# MicroBlue-CPU_PSU_1_0_rdob-millable.net
KiCad netlist of a schematic drawn in EAGLE
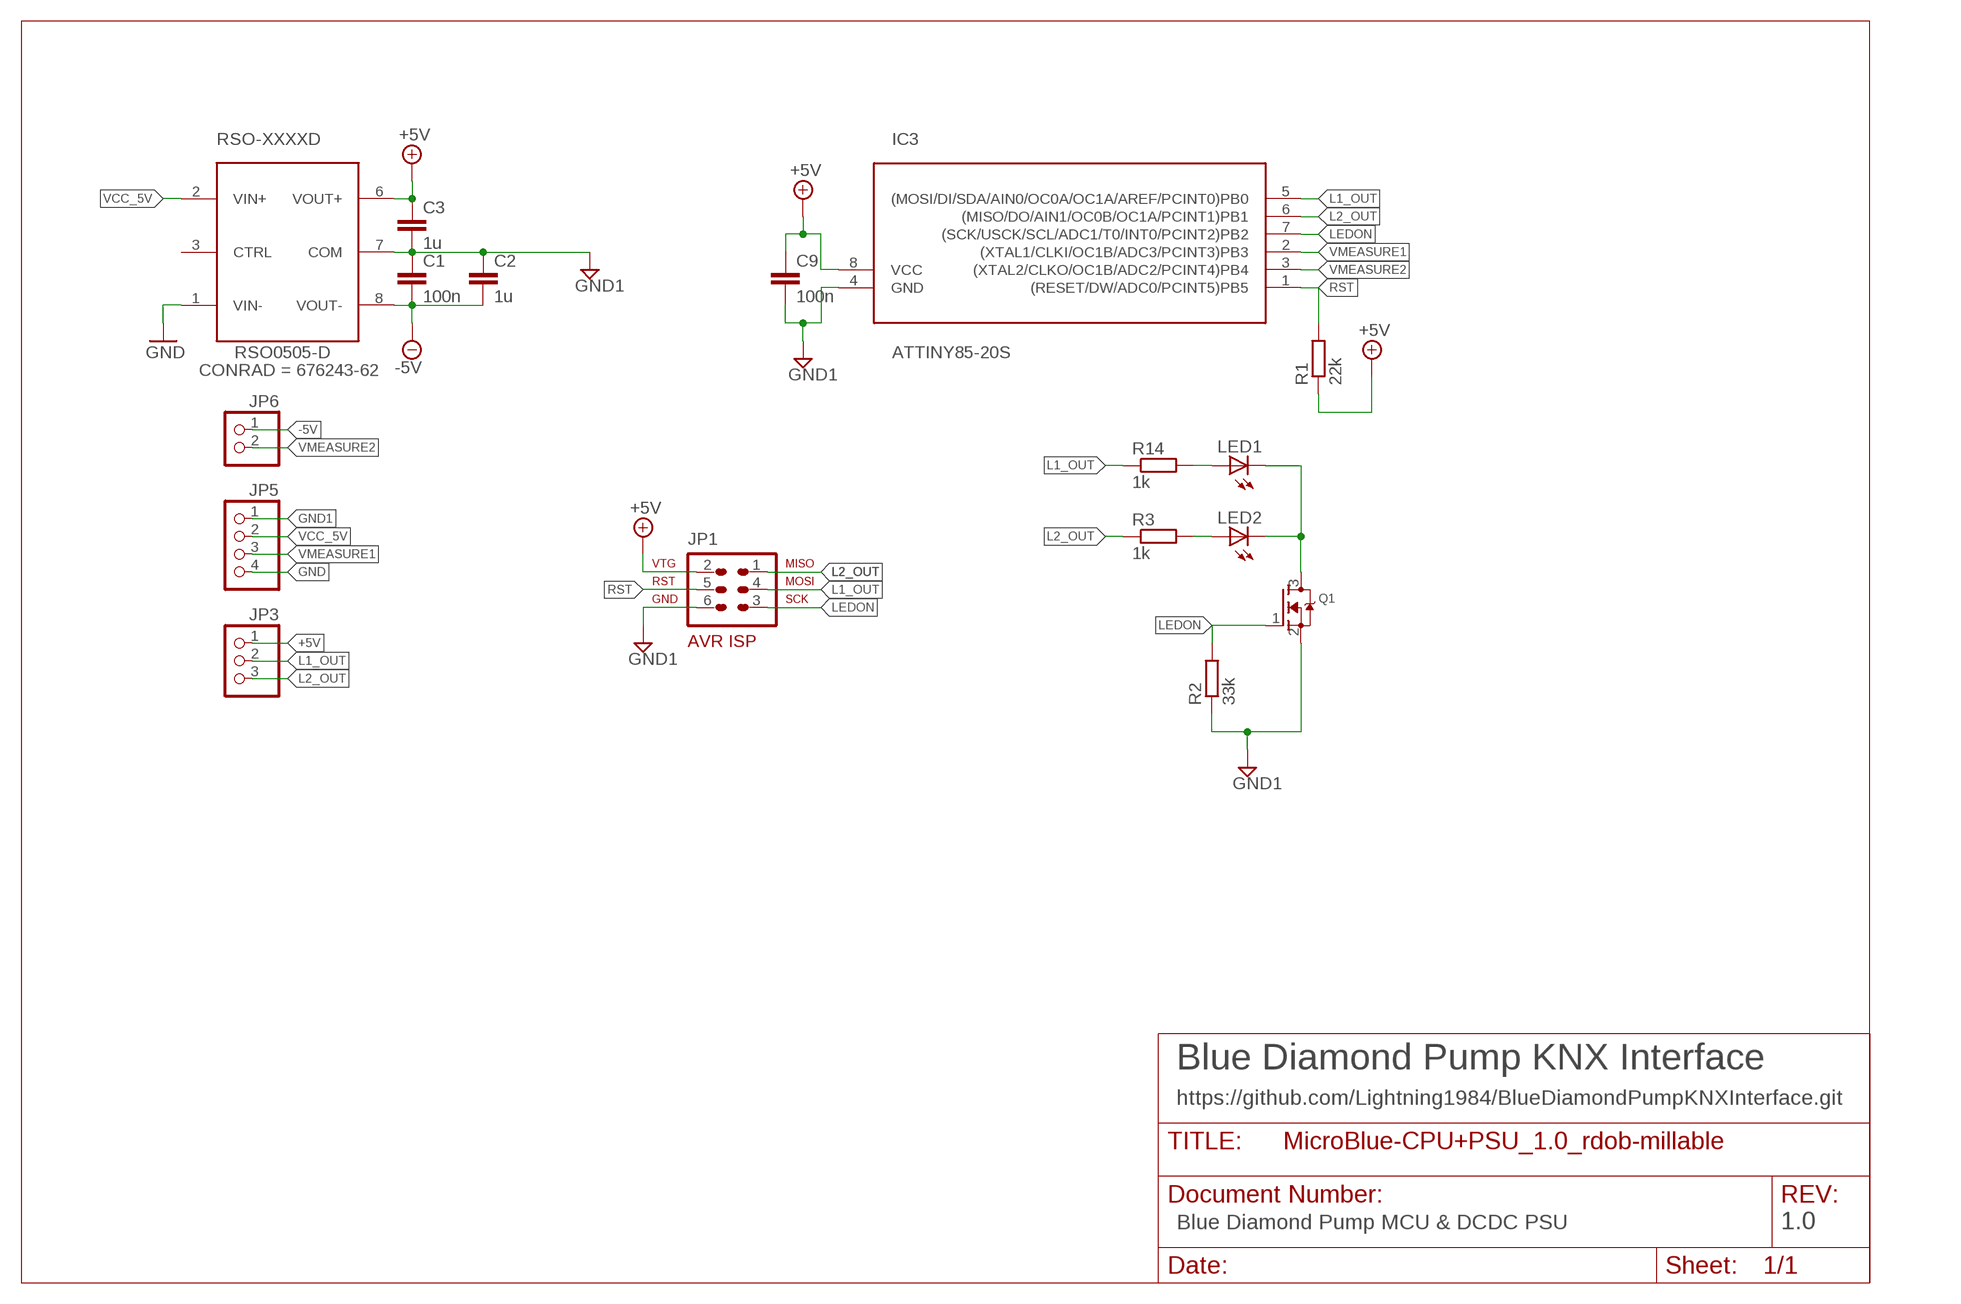
[diagram p0: schematic, sheet 1]

(export (version "E")
  (design (tool "Eeschema 10.0.6"))
  (components
    (comp (ref "C1")
      (value "100n")
      (footprint "eagle-import:C0805K")
      (libsource (lib "eagle-import") (part "C-EUC0805K"))
    )
    (comp (ref "C2")
      (value "1u")
      (footprint "eagle-import:C0805K")
      (libsource (lib "eagle-import") (part "C-EUC0805K"))
    )
    (comp (ref "C3")
      (value "1u")
      (footprint "eagle-import:C0805K")
      (libsource (lib "eagle-import") (part "C-EUC0805K"))
    )
    (comp (ref "C9")
      (value "100n")
      (footprint "eagle-import:C0805K")
      (libsource (lib "eagle-import") (part "C-EUC0805K"))
    )
    (comp (ref "IC3")
      (value "ATTINY85-20S")
      (footprint "eagle-import:SOIC8")
      (libsource (lib "eagle-import") (part "ATTINY85S-20"))
    )
    (comp (ref "JP1")
      (value "AVR-ISP-6R")
      (footprint "eagle-import:AVR-ISP-6R")
      (libsource (lib "eagle-import") (part "AVR-ISP-6R"))
    )
    (comp (ref "JP3")
      (value "PINHD-1X03_2.54-0.90MM-DRILL")
      (footprint "eagle-import:1X03-0.90DRILL")
      (libsource (lib "eagle-import") (part "PINHD-1X03_2.54-0.90MM-DRILL"))
    )
    (comp (ref "JP5")
      (value "PINHD-1X04_2.54-0.90MM-DRILL")
      (footprint "eagle-import:1X04-0.90DRILL")
      (libsource (lib "eagle-import") (part "PINHD-1X04_2.54-0.90MM-DRILL"))
    )
    (comp (ref "JP6")
      (value "PINHD-1X02_2.54-0.90MM-DRILL")
      (footprint "eagle-import:1X02-0.90DRILL")
      (libsource (lib "eagle-import") (part "PINHD-1X02_2.54-0.90MM-DRILL"))
    )
    (comp (ref "LED1")
      (value "LEDSMT1206")
      (footprint "eagle-import:1206")
      (libsource (lib "eagle-import") (part "LEDSMT1206"))
    )
    (comp (ref "LED2")
      (value "LEDSMT1206")
      (footprint "eagle-import:1206")
      (libsource (lib "eagle-import") (part "LEDSMT1206"))
    )
    (comp (ref "Q1")
      (value "MOSFET-NREFLOW")
      (footprint "eagle-import:SOT23")
      (libsource (lib "eagle-import") (part "MOSFET-NREFLOW"))
    )
    (comp (ref "R1")
      (value "22k")
      (footprint "eagle-import:R1206")
      (libsource (lib "eagle-import") (part "R-EU_R1206"))
    )
    (comp (ref "R2")
      (value "33k")
      (footprint "eagle-import:R1206")
      (libsource (lib "eagle-import") (part "R-EU_R1206"))
    )
    (comp (ref "R3")
      (value "1k")
      (footprint "eagle-import:R1206")
      (libsource (lib "eagle-import") (part "R-EU_R1206"))
    )
    (comp (ref "R14")
      (value "1k")
      (footprint "eagle-import:R1206")
      (libsource (lib "eagle-import") (part "R-EU_R1206"))
    )
    (comp (ref "RSO0505-D")
      (value "RSO-0505D")
      (footprint "eagle-import:RSO-XXXX")
      (fields (field (name "CONRAD") "676243-62") (field (name "DEVICE") "RSO0505-D"))
      (libsource (lib "eagle-import") (part "RSO-XXXXD_RSO-XXXXD"))
    )
  )
  (nets
    (net (code "1") (name "+5V") (class "Default")
      (node (ref "C3") (pin "1") (pinfunction "1_1") (pintype "passive"))
      (node (ref "C9") (pin "1") (pinfunction "1_1") (pintype "passive"))
      (node (ref "IC3") (pin "8") (pinfunction "VCC_8") (pintype "bidirectional"))
      (node (ref "JP1") (pin "2") (pinfunction "2_2") (pintype "passive"))
      (node (ref "JP3") (pin "1") (pinfunction "1_1") (pintype "passive"))
      (node (ref "R1") (pin "1") (pinfunction "1_1") (pintype "passive"))
      (node (ref "RSO0505-D") (pin "6") (pinfunction "VOUT+_6") (pintype "power_in"))
    )
    (net (code "2") (name "-5V") (class "Default")
      (node (ref "C1") (pin "2") (pinfunction "2_2") (pintype "passive"))
      (node (ref "C2") (pin "2") (pinfunction "2_2") (pintype "passive"))
      (node (ref "JP6") (pin "1") (pinfunction "1_1") (pintype "passive"))
      (node (ref "RSO0505-D") (pin "8") (pinfunction "VOUT-_8") (pintype "power_in"))
    )
    (net (code "3") (name "GND") (class "Default")
      (node (ref "JP5") (pin "4") (pinfunction "4_4") (pintype "passive"))
      (node (ref "RSO0505-D") (pin "1") (pinfunction "VIN-_1") (pintype "power_in"))
    )
    (net (code "4") (name "GND1") (class "Default")
      (node (ref "C1") (pin "1") (pinfunction "1_1") (pintype "passive"))
      (node (ref "C2") (pin "1") (pinfunction "1_1") (pintype "passive"))
      (node (ref "C3") (pin "2") (pinfunction "2_2") (pintype "passive"))
      (node (ref "C9") (pin "2") (pinfunction "2_2") (pintype "passive"))
      (node (ref "IC3") (pin "4") (pinfunction "GND_4") (pintype "bidirectional"))
      (node (ref "JP1") (pin "6") (pinfunction "6_6") (pintype "passive"))
      (node (ref "JP5") (pin "1") (pinfunction "1_1") (pintype "passive"))
      (node (ref "Q1") (pin "2") (pinfunction "S_2") (pintype "bidirectional"))
      (node (ref "R2") (pin "1") (pinfunction "1_1") (pintype "passive"))
      (node (ref "RSO0505-D") (pin "7") (pinfunction "COM_7") (pintype "power_in"))
    )
    (net (code "5") (name "L1_OUT") (class "Default")
      (node (ref "IC3") (pin "5") (pinfunction "(MOSI/DI/SDA/AIN0/OC0A/OC1A/AREF/PCINT0)PB0_5") (pintype "bidirectional"))
      (node (ref "JP1") (pin "4") (pinfunction "4_4") (pintype "passive"))
      (node (ref "JP3") (pin "2") (pinfunction "2_2") (pintype "passive"))
      (node (ref "R14") (pin "1") (pinfunction "1_1") (pintype "passive"))
    )
    (net (code "6") (name "L2_OUT") (class "Default")
      (node (ref "IC3") (pin "6") (pinfunction "(MISO/DO/AIN1/OC0B/OC1A/PCINT1)PB1_6") (pintype "bidirectional"))
      (node (ref "JP1") (pin "1") (pinfunction "1_1") (pintype "passive"))
      (node (ref "JP3") (pin "3") (pinfunction "3_3") (pintype "passive"))
      (node (ref "R3") (pin "1") (pinfunction "1_1") (pintype "passive"))
    )
    (net (code "7") (name "LEDON") (class "Default")
      (node (ref "IC3") (pin "7") (pinfunction "(SCK/USCK/SCL/ADC1/T0/INT0/PCINT2)PB2_7") (pintype "bidirectional"))
      (node (ref "JP1") (pin "3") (pinfunction "3_3") (pintype "passive"))
      (node (ref "Q1") (pin "1") (pinfunction "G_1") (pintype "bidirectional"))
      (node (ref "R2") (pin "2") (pinfunction "2_2") (pintype "passive"))
    )
    (net (code "8") (name "Net-(LED1-PadA)") (class "Default")
      (node (ref "LED1") (pin "A") (pinfunction "A_A") (pintype "passive"))
      (node (ref "R14") (pin "2") (pinfunction "2_2") (pintype "passive"))
    )
    (net (code "9") (name "Net-(LED2-PadA)") (class "Default")
      (node (ref "LED2") (pin "A") (pinfunction "A_A") (pintype "passive"))
      (node (ref "R3") (pin "2") (pinfunction "2_2") (pintype "passive"))
    )
    (net (code "10") (name "Net-(Q1-D)") (class "Default")
      (node (ref "LED1") (pin "C") (pinfunction "C_C") (pintype "passive"))
      (node (ref "LED2") (pin "C") (pinfunction "C_C") (pintype "passive"))
      (node (ref "Q1") (pin "3") (pinfunction "D_3") (pintype "bidirectional"))
    )
    (net (code "11") (name "RST") (class "Default")
      (node (ref "IC3") (pin "1") (pinfunction "(RESET/DW/ADC0/PCINT5)PB5_1") (pintype "bidirectional"))
      (node (ref "JP1") (pin "5") (pinfunction "5_5") (pintype "passive"))
      (node (ref "R1") (pin "2") (pinfunction "2_2") (pintype "passive"))
    )
    (net (code "12") (name "VCC_5V") (class "Default")
      (node (ref "JP5") (pin "2") (pinfunction "2_2") (pintype "passive"))
      (node (ref "RSO0505-D") (pin "2") (pinfunction "VIN+_2") (pintype "power_in"))
    )
    (net (code "13") (name "VMEASURE1") (class "Default")
      (node (ref "IC3") (pin "2") (pinfunction "(XTAL1/CLKI/OC1B/ADC3/PCINT3)PB3_2") (pintype "bidirectional"))
      (node (ref "JP5") (pin "3") (pinfunction "3_3") (pintype "passive"))
    )
    (net (code "14") (name "VMEASURE2") (class "Default")
      (node (ref "IC3") (pin "3") (pinfunction "(XTAL2/CLKO/OC1B/ADC2/PCINT4)PB4_3") (pintype "bidirectional"))
      (node (ref "JP6") (pin "2") (pinfunction "2_2") (pintype "passive"))
    )
    (net (code "15") (name "unconnected-(RSO0505-D-CTRL-Pad3)") (class "Default")
      (node (ref "RSO0505-D") (pin "3") (pinfunction "CTRL_3") (pintype "input"))
    )
  )
)
